# connector.net
KiCad netlist of a schematic drawn in Altium Designer
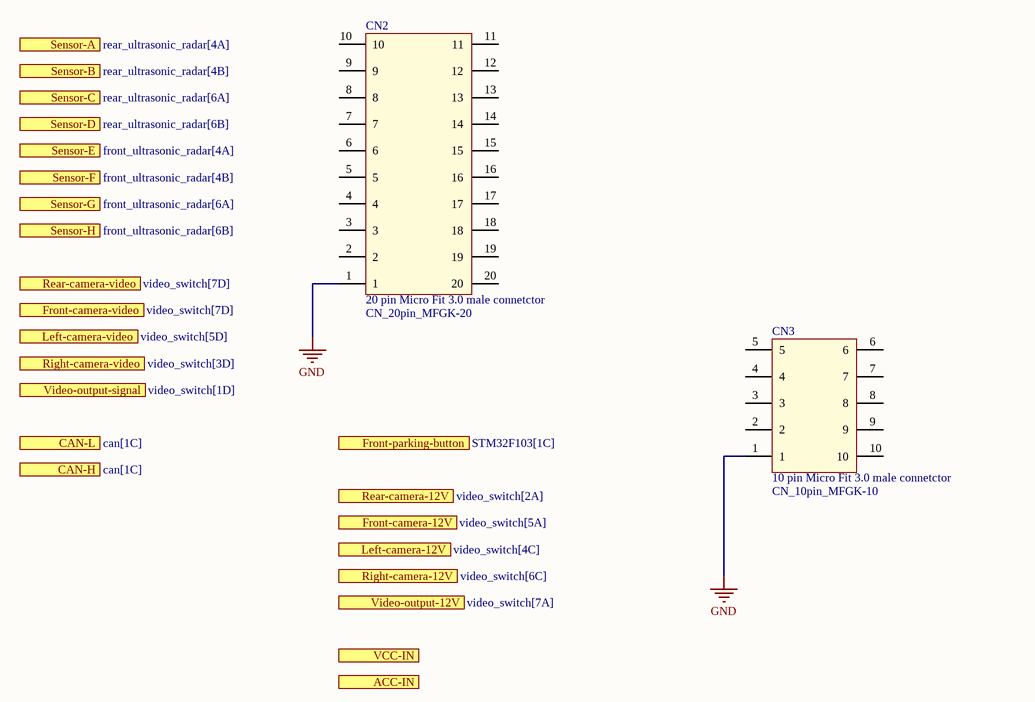
[diagram p0: connector.SchDoc]

(export (version "E")
  (design (tool "Eeschema 10.0.6"))
  (components
    (comp (ref "CN2")
      (value "20 pin Micro Fit 3.0 male connetctor")
      (footprint "CN_20pin_MFGK-20")
      (description "Molex, Micro-Fit 3.0, 43045, 20 Way, 2 Row, Right Angle PCB Header")
      (fields (field (name "VALUE1") "CN_20pin_MFGK-20") (field (name "MANUFACTURER") "Molex"))
      (libsource (lib "DSW_Lib") (part "CN_20pin_MFGK-20"))
    )
    (comp (ref "CN3")
      (value "10 pin Micro Fit 3.0 male connetctor")
      (footprint "CN_10pin_MFGK-10")
      (description "Molex, Micro-Fit 3.0, 43045, 10 Way, 2 Row, Right Angle PCB Header")
      (fields (field (name "VALUE1") "CN_10pin_MFGK-10") (field (name "MANUFACTURER") "Molex"))
      (libsource (lib "DSW_Lib") (part "CN_10pin_MFGK-10"))
    )
  )
  (nets
    (net (code "24") (name "GND") (class "Default")
      (node (ref "CN2") (pin "1") (pinfunction "1_1") (pintype "passive"))
      (node (ref "CN3") (pin "1") (pinfunction "1_1") (pintype "passive"))
    )
    (net (code "25") (name "unconnected-(CN2-Pad2)") (class "Default")
      (node (ref "CN2") (pin "2") (pinfunction "2_2") (pintype "passive"))
    )
    (net (code "26") (name "unconnected-(CN2-Pad3)") (class "Default")
      (node (ref "CN2") (pin "3") (pinfunction "3_3") (pintype "passive"))
    )
    (net (code "27") (name "unconnected-(CN2-Pad4)") (class "Default")
      (node (ref "CN2") (pin "4") (pinfunction "4_4") (pintype "passive"))
    )
    (net (code "28") (name "unconnected-(CN2-Pad5)") (class "Default")
      (node (ref "CN2") (pin "5") (pinfunction "5_5") (pintype "passive"))
    )
    (net (code "29") (name "unconnected-(CN2-Pad6)") (class "Default")
      (node (ref "CN2") (pin "6") (pinfunction "6_6") (pintype "passive"))
    )
    (net (code "30") (name "unconnected-(CN2-Pad7)") (class "Default")
      (node (ref "CN2") (pin "7") (pinfunction "7_7") (pintype "passive"))
    )
    (net (code "31") (name "unconnected-(CN2-Pad8)") (class "Default")
      (node (ref "CN2") (pin "8") (pinfunction "8_8") (pintype "passive"))
    )
    (net (code "32") (name "unconnected-(CN2-Pad9)") (class "Default")
      (node (ref "CN2") (pin "9") (pinfunction "9_9") (pintype "passive"))
    )
    (net (code "33") (name "unconnected-(CN2-Pad10)") (class "Default")
      (node (ref "CN2") (pin "10") (pinfunction "10_10") (pintype "passive"))
    )
    (net (code "34") (name "unconnected-(CN2-Pad11)") (class "Default")
      (node (ref "CN2") (pin "11") (pinfunction "11_11") (pintype "passive"))
    )
    (net (code "35") (name "unconnected-(CN2-Pad12)") (class "Default")
      (node (ref "CN2") (pin "12") (pinfunction "12_12") (pintype "passive"))
    )
    (net (code "36") (name "unconnected-(CN2-Pad13)") (class "Default")
      (node (ref "CN2") (pin "13") (pinfunction "13_13") (pintype "passive"))
    )
    (net (code "37") (name "unconnected-(CN2-Pad14)") (class "Default")
      (node (ref "CN2") (pin "14") (pinfunction "14_14") (pintype "passive"))
    )
    (net (code "38") (name "unconnected-(CN2-Pad15)") (class "Default")
      (node (ref "CN2") (pin "15") (pinfunction "15_15") (pintype "passive"))
    )
    (net (code "39") (name "unconnected-(CN2-Pad16)") (class "Default")
      (node (ref "CN2") (pin "16") (pinfunction "16_16") (pintype "passive"))
    )
    (net (code "40") (name "unconnected-(CN2-Pad17)") (class "Default")
      (node (ref "CN2") (pin "17") (pinfunction "17_17") (pintype "passive"))
    )
    (net (code "41") (name "unconnected-(CN2-Pad18)") (class "Default")
      (node (ref "CN2") (pin "18") (pinfunction "18_18") (pintype "passive"))
    )
    (net (code "42") (name "unconnected-(CN2-Pad19)") (class "Default")
      (node (ref "CN2") (pin "19") (pinfunction "19_19") (pintype "passive"))
    )
    (net (code "43") (name "unconnected-(CN2-Pad20)") (class "Default")
      (node (ref "CN2") (pin "20") (pinfunction "20_20") (pintype "passive"))
    )
    (net (code "44") (name "unconnected-(CN3-Pad2)") (class "Default")
      (node (ref "CN3") (pin "2") (pinfunction "2_2") (pintype "passive"))
    )
    (net (code "45") (name "unconnected-(CN3-Pad3)") (class "Default")
      (node (ref "CN3") (pin "3") (pinfunction "3_3") (pintype "passive"))
    )
    (net (code "46") (name "unconnected-(CN3-Pad4)") (class "Default")
      (node (ref "CN3") (pin "4") (pinfunction "4_4") (pintype "passive"))
    )
    (net (code "47") (name "unconnected-(CN3-Pad5)") (class "Default")
      (node (ref "CN3") (pin "5") (pinfunction "5_5") (pintype "passive"))
    )
    (net (code "48") (name "unconnected-(CN3-Pad6)") (class "Default")
      (node (ref "CN3") (pin "6") (pinfunction "6_6") (pintype "passive"))
    )
    (net (code "49") (name "unconnected-(CN3-Pad7)") (class "Default")
      (node (ref "CN3") (pin "7") (pinfunction "7_7") (pintype "passive"))
    )
    (net (code "50") (name "unconnected-(CN3-Pad8)") (class "Default")
      (node (ref "CN3") (pin "8") (pinfunction "8_8") (pintype "passive"))
    )
    (net (code "51") (name "unconnected-(CN3-Pad9)") (class "Default")
      (node (ref "CN3") (pin "9") (pinfunction "9_9") (pintype "passive"))
    )
    (net (code "52") (name "unconnected-(CN3-Pad10)") (class "Default")
      (node (ref "CN3") (pin "10") (pinfunction "10_10") (pintype "passive"))
    )
  )
)
